# rapidshark-main-breakout-top-mk-1_2.net
KiCad netlist of a schematic drawn in EAGLE
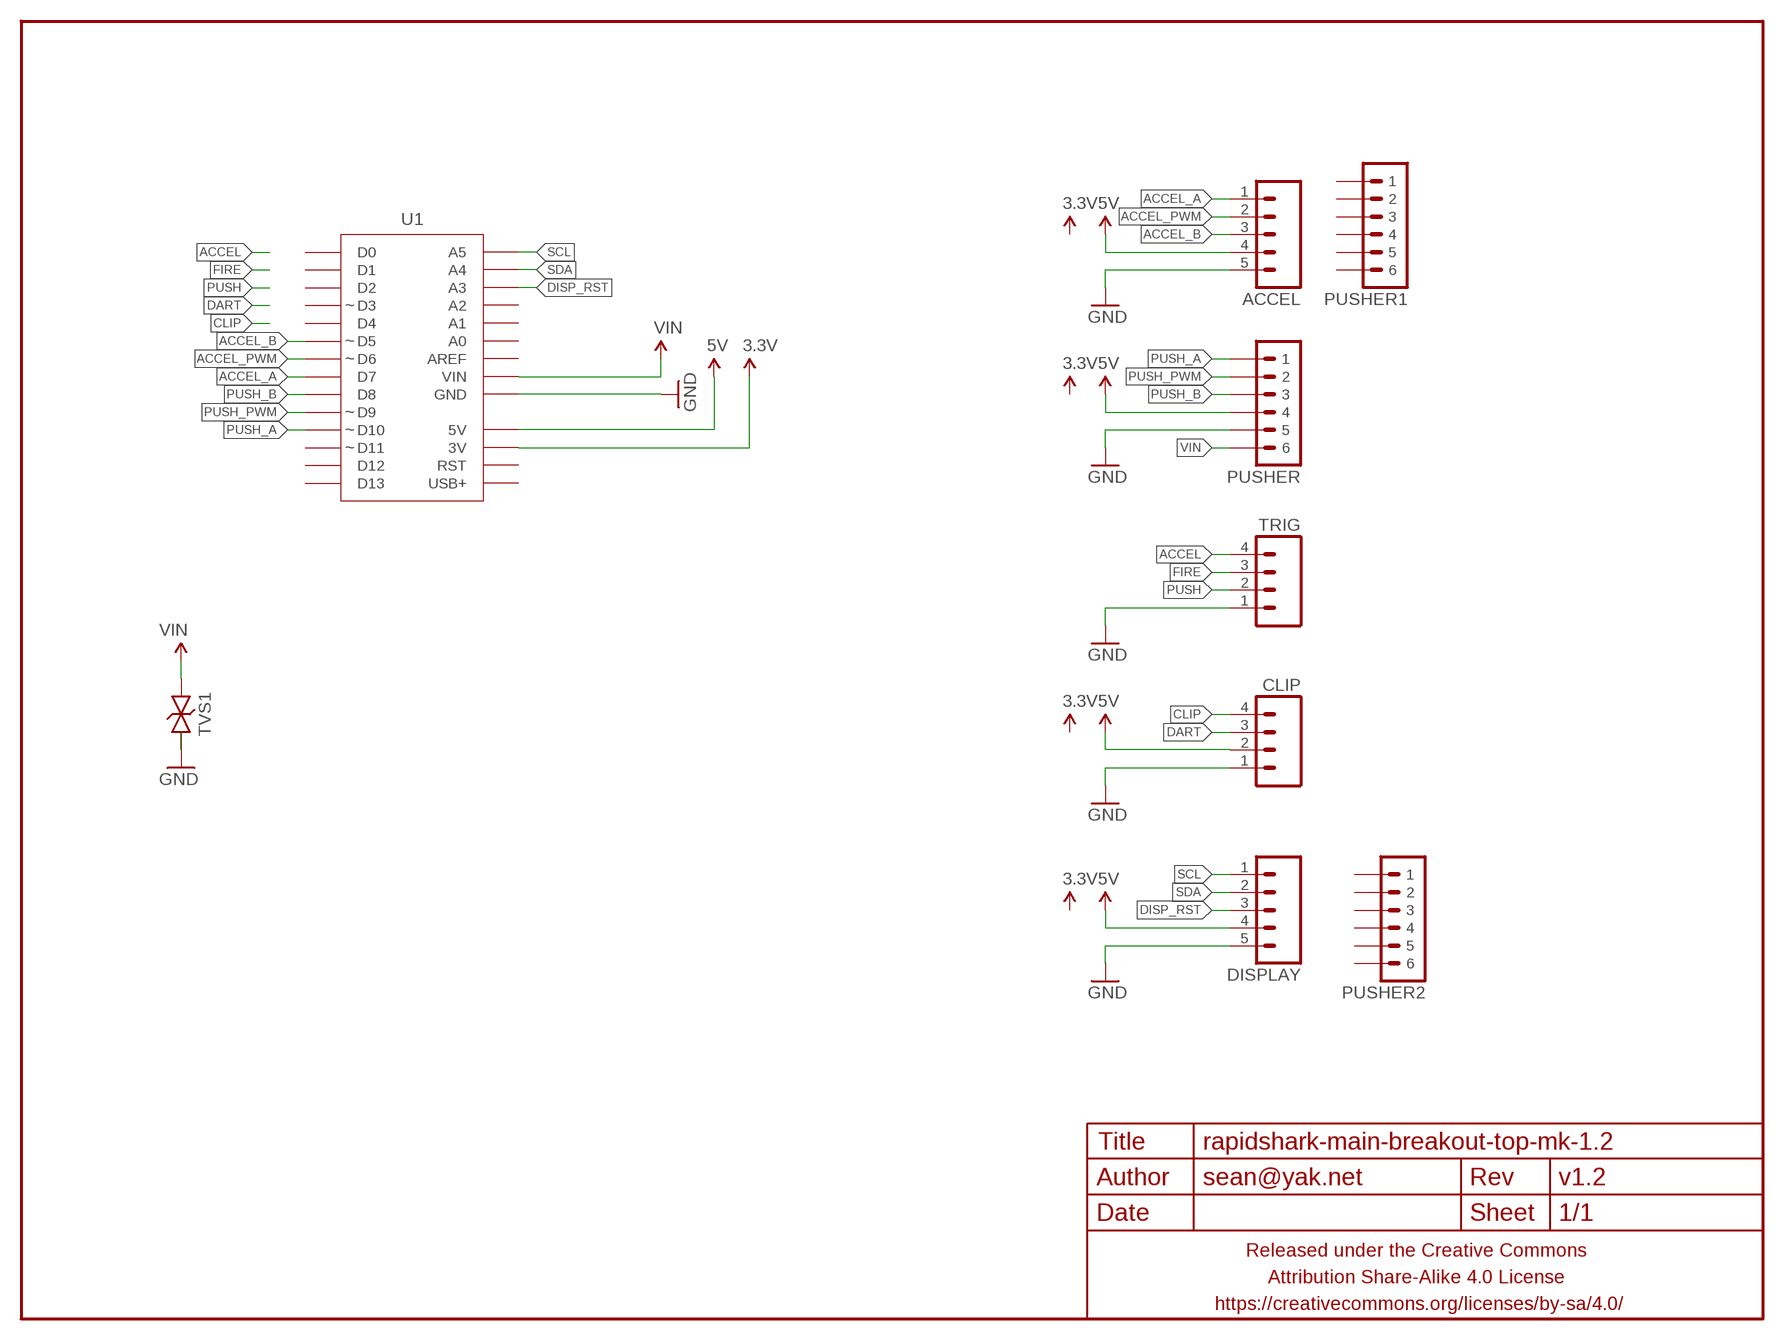
[diagram p0: schematic, sheet 1]

(export (version "E")
  (design (tool "Eeschema 10.0.6"))
  (components
    (comp (ref "ACCEL")
      (value "M05JST-PH-VERT-PTH")
      (footprint "eagle-import:JST-5-PH-VERT-PTH")
      (libsource (lib "eagle-import") (part "M05JST-PH-VERT-PTH"))
    )
    (comp (ref "CLIP")
      (value "M04JST-PTH-VERT")
      (footprint "eagle-import:JST-4-PH-VERT-PTH")
      (libsource (lib "eagle-import") (part "M04JST-PTH-VERT"))
    )
    (comp (ref "DISPLAY")
      (value "M05JST-PH-VERT-PTH")
      (footprint "eagle-import:JST-5-PH-VERT-PTH")
      (libsource (lib "eagle-import") (part "M05JST-PH-VERT-PTH"))
    )
    (comp (ref "FRAME1")
      (value "FRAME-LETTERNO_PACKAGE")
      (footprint "eagle-import:DUMMY")
      (fields (field (name "DESIGNER") "sean@yak.net") (field (name "VERSION") "v1.2"))
      (libsource (lib "eagle-import") (part "FRAME-LETTERNO_PACKAGE"))
    )
    (comp (ref "PUSHER")
      (value "M06JST-PH-PTH-VERT")
      (footprint "eagle-import:JST-6-PH-VERT-PTH")
      (libsource (lib "eagle-import") (part "M06JST-PH-PTH-VERT"))
    )
    (comp (ref "PUSHER1")
      (value "M06JST-PH-PTH-VERT")
      (footprint "eagle-import:JST-6-PH-VERT-PTH")
      (libsource (lib "eagle-import") (part "M06JST-PH-PTH-VERT"))
    )
    (comp (ref "PUSHER2")
      (value "M06JST-PH-PTH-VERT")
      (footprint "eagle-import:JST-6-PH-VERT-PTH")
      (libsource (lib "eagle-import") (part "M06JST-PH-PTH-VERT"))
    )
    (comp (ref "TRIG")
      (value "M04JST-PTH-VERT")
      (footprint "eagle-import:JST-4-PH-VERT-PTH")
      (libsource (lib "eagle-import") (part "M04JST-PTH-VERT"))
    )
    (comp (ref "TVS1")
      (value "TVSDO-41-8.89MM")
      (footprint "eagle-import:DO-41-TVS-BI-8.89MM")
      (libsource (lib "eagle-import") (part "TVSDO-41-8.89MM"))
    )
    (comp (ref "U1")
      (value "ADAFRUIT_METRO_MININOSILK-ABMBI")
      (footprint "eagle-import:ADAFRUIT_METRO_MINI_FLIPPED")
      (libsource (lib "eagle-import") (part "ADAFRUIT_METRO_MININOSILK-ABMBI"))
    )
  )
  (nets
    (net (code "1") (name "3.3V") (class "Default")
      (node (ref "U1") (pin "17") (pinfunction "3V_17") (pintype "bidirectional"))
    )
    (net (code "2") (name "5V") (class "Default")
      (node (ref "ACCEL") (pin "4") (pinfunction "4_4") (pintype "passive"))
      (node (ref "CLIP") (pin "2") (pinfunction "2_2") (pintype "passive"))
      (node (ref "DISPLAY") (pin "4") (pinfunction "4_4") (pintype "passive"))
      (node (ref "PUSHER") (pin "4") (pinfunction "4_4") (pintype "passive"))
      (node (ref "U1") (pin "18") (pinfunction "5V_18") (pintype "bidirectional"))
    )
    (net (code "3") (name "ACCEL") (class "Default")
      (node (ref "TRIG") (pin "4") (pinfunction "4_4") (pintype "passive"))
    )
    (net (code "4") (name "ACCEL_A") (class "Default")
      (node (ref "ACCEL") (pin "1") (pinfunction "1_1") (pintype "passive"))
      (node (ref "U1") (pin "8") (pinfunction "D7_8") (pintype "bidirectional"))
    )
    (net (code "5") (name "ACCEL_B") (class "Default")
      (node (ref "ACCEL") (pin "3") (pinfunction "3_3") (pintype "passive"))
      (node (ref "U1") (pin "6") (pinfunction "D5_6") (pintype "bidirectional"))
    )
    (net (code "6") (name "ACCEL_PWM") (class "Default")
      (node (ref "ACCEL") (pin "2") (pinfunction "2_2") (pintype "passive"))
      (node (ref "U1") (pin "7") (pinfunction "D6_7") (pintype "bidirectional"))
    )
    (net (code "7") (name "CLIP") (class "Default")
      (node (ref "CLIP") (pin "4") (pinfunction "4_4") (pintype "passive"))
    )
    (net (code "8") (name "DART") (class "Default")
      (node (ref "CLIP") (pin "3") (pinfunction "3_3") (pintype "passive"))
    )
    (net (code "9") (name "DISP_RST") (class "Default")
      (node (ref "DISPLAY") (pin "3") (pinfunction "3_3") (pintype "passive"))
      (node (ref "U1") (pin "26") (pinfunction "A3_26") (pintype "bidirectional"))
    )
    (net (code "10") (name "FIRE") (class "Default")
      (node (ref "TRIG") (pin "3") (pinfunction "3_3") (pintype "passive"))
    )
    (net (code "11") (name "GND") (class "Default")
      (node (ref "ACCEL") (pin "5") (pinfunction "5_5") (pintype "passive"))
      (node (ref "CLIP") (pin "1") (pinfunction "1_1") (pintype "passive"))
      (node (ref "DISPLAY") (pin "5") (pinfunction "5_5") (pintype "passive"))
      (node (ref "PUSHER") (pin "5") (pinfunction "5_5") (pintype "passive"))
      (node (ref "TRIG") (pin "1") (pinfunction "1_1") (pintype "passive"))
      (node (ref "TVS1") (pin "P$1") (pinfunction "1_P$1") (pintype "passive"))
      (node (ref "U1") (pin "19") (pinfunction "GND_19") (pintype "bidirectional"))
      (node (ref "U1") (pin "20") (pinfunction "GND_20") (pintype "bidirectional"))
    )
    (net (code "12") (name "PUSH") (class "Default")
      (node (ref "TRIG") (pin "2") (pinfunction "2_2") (pintype "passive"))
    )
    (net (code "13") (name "PUSH_A") (class "Default")
      (node (ref "PUSHER") (pin "1") (pinfunction "1_1") (pintype "passive"))
      (node (ref "U1") (pin "11") (pinfunction "D10_11") (pintype "bidirectional"))
    )
    (net (code "14") (name "PUSH_B") (class "Default")
      (node (ref "PUSHER") (pin "3") (pinfunction "3_3") (pintype "passive"))
      (node (ref "U1") (pin "9") (pinfunction "D8_9") (pintype "bidirectional"))
    )
    (net (code "15") (name "PUSH_PWM") (class "Default")
      (node (ref "PUSHER") (pin "2") (pinfunction "2_2") (pintype "passive"))
      (node (ref "U1") (pin "10") (pinfunction "D9_10") (pintype "bidirectional"))
    )
    (net (code "16") (name "SCL") (class "Default")
      (node (ref "DISPLAY") (pin "1") (pinfunction "1_1") (pintype "passive"))
      (node (ref "U1") (pin "28") (pinfunction "A5_28") (pintype "bidirectional"))
    )
    (net (code "17") (name "SDA") (class "Default")
      (node (ref "DISPLAY") (pin "2") (pinfunction "2_2") (pintype "passive"))
      (node (ref "U1") (pin "27") (pinfunction "A4_27") (pintype "bidirectional"))
    )
    (net (code "18") (name "VIN") (class "Default")
      (node (ref "PUSHER") (pin "6") (pinfunction "6_6") (pintype "passive"))
      (node (ref "TVS1") (pin "P$2") (pinfunction "2_P$2") (pintype "passive"))
      (node (ref "U1") (pin "21") (pinfunction "VIN_21") (pintype "bidirectional"))
    )
    (net (code "19") (name "unconnected-(PUSHER1-Pad1)") (class "Default")
      (node (ref "PUSHER1") (pin "1") (pinfunction "1_1") (pintype "passive"))
    )
    (net (code "20") (name "unconnected-(PUSHER1-Pad2)") (class "Default")
      (node (ref "PUSHER1") (pin "2") (pinfunction "2_2") (pintype "passive"))
    )
    (net (code "21") (name "unconnected-(PUSHER1-Pad3)") (class "Default")
      (node (ref "PUSHER1") (pin "3") (pinfunction "3_3") (pintype "passive"))
    )
    (net (code "22") (name "unconnected-(PUSHER1-Pad4)") (class "Default")
      (node (ref "PUSHER1") (pin "4") (pinfunction "4_4") (pintype "passive"))
    )
    (net (code "23") (name "unconnected-(PUSHER1-Pad5)") (class "Default")
      (node (ref "PUSHER1") (pin "5") (pinfunction "5_5") (pintype "passive"))
    )
    (net (code "24") (name "unconnected-(PUSHER1-Pad6)") (class "Default")
      (node (ref "PUSHER1") (pin "6") (pinfunction "6_6") (pintype "passive"))
    )
    (net (code "25") (name "unconnected-(PUSHER2-Pad1)") (class "Default")
      (node (ref "PUSHER2") (pin "1") (pinfunction "1_1") (pintype "passive"))
    )
    (net (code "26") (name "unconnected-(PUSHER2-Pad2)") (class "Default")
      (node (ref "PUSHER2") (pin "2") (pinfunction "2_2") (pintype "passive"))
    )
    (net (code "27") (name "unconnected-(PUSHER2-Pad3)") (class "Default")
      (node (ref "PUSHER2") (pin "3") (pinfunction "3_3") (pintype "passive"))
    )
    (net (code "28") (name "unconnected-(PUSHER2-Pad4)") (class "Default")
      (node (ref "PUSHER2") (pin "4") (pinfunction "4_4") (pintype "passive"))
    )
    (net (code "29") (name "unconnected-(PUSHER2-Pad5)") (class "Default")
      (node (ref "PUSHER2") (pin "5") (pinfunction "5_5") (pintype "passive"))
    )
    (net (code "30") (name "unconnected-(PUSHER2-Pad6)") (class "Default")
      (node (ref "PUSHER2") (pin "6") (pinfunction "6_6") (pintype "passive"))
    )
    (net (code "31") (name "unconnected-(U1-A0-Pad23)") (class "Default")
      (node (ref "U1") (pin "23") (pinfunction "A0_23") (pintype "bidirectional"))
    )
    (net (code "32") (name "unconnected-(U1-A1-Pad24)") (class "Default")
      (node (ref "U1") (pin "24") (pinfunction "A1_24") (pintype "bidirectional"))
    )
    (net (code "33") (name "unconnected-(U1-A2-Pad25)") (class "Default")
      (node (ref "U1") (pin "25") (pinfunction "A2_25") (pintype "bidirectional"))
    )
    (net (code "34") (name "unconnected-(U1-AREF-Pad22)") (class "Default")
      (node (ref "U1") (pin "22") (pinfunction "AREF_22") (pintype "bidirectional"))
    )
    (net (code "35") (name "unconnected-(U1-D0-Pad1)") (class "Default")
      (node (ref "U1") (pin "1") (pinfunction "D0_1") (pintype "bidirectional"))
    )
    (net (code "36") (name "unconnected-(U1-D1-Pad2)") (class "Default")
      (node (ref "U1") (pin "2") (pinfunction "D1_2") (pintype "bidirectional"))
    )
    (net (code "37") (name "unconnected-(U1-D2-Pad3)") (class "Default")
      (node (ref "U1") (pin "3") (pinfunction "D2_3") (pintype "bidirectional"))
    )
    (net (code "38") (name "unconnected-(U1-D3-Pad4)") (class "Default")
      (node (ref "U1") (pin "4") (pinfunction "D3_4") (pintype "bidirectional"))
    )
    (net (code "39") (name "unconnected-(U1-D4-Pad5)") (class "Default")
      (node (ref "U1") (pin "5") (pinfunction "D4_5") (pintype "bidirectional"))
    )
    (net (code "40") (name "unconnected-(U1-D11-Pad12)") (class "Default")
      (node (ref "U1") (pin "12") (pinfunction "D11_12") (pintype "bidirectional"))
    )
    (net (code "41") (name "unconnected-(U1-D12-Pad13)") (class "Default")
      (node (ref "U1") (pin "13") (pinfunction "D12_13") (pintype "bidirectional"))
    )
    (net (code "42") (name "unconnected-(U1-D13-Pad14)") (class "Default")
      (node (ref "U1") (pin "14") (pinfunction "D13_14") (pintype "bidirectional"))
    )
    (net (code "43") (name "unconnected-(U1-RST-Pad16)") (class "Default")
      (node (ref "U1") (pin "16") (pinfunction "RST_16") (pintype "bidirectional"))
    )
    (net (code "44") (name "unconnected-(U1-USB+-Pad15)") (class "Default")
      (node (ref "U1") (pin "15") (pinfunction "USB+_15") (pintype "bidirectional"))
    )
  )
)
